# 3V3_BUCK.net
KiCad netlist of a schematic drawn in Altium Designer
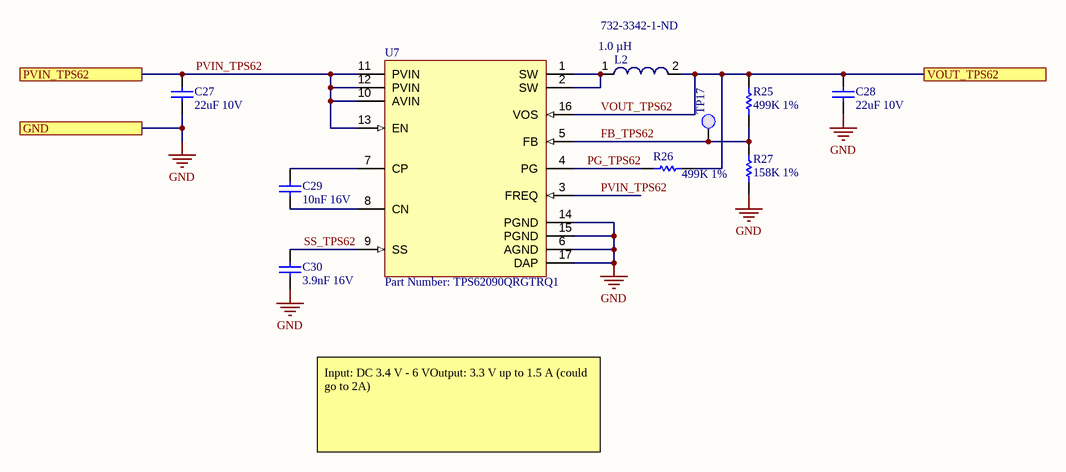
[diagram p0: 3V3_BUCK.SchDoc]

(export (version "E")
  (design (tool "Eeschema 10.0.6"))
  (components
    (comp (ref "C27")
      (value "22uF 10V")
      (footprint "CAPC0805(2012)145_N")
      (description "CAP 22uF 10V ±20% 0805 (2012 Metric) Thickness 1.45mm SMD")
      (fields (field (name "TOLERANCE") "Â±20%"))
      (libsource (lib "Altium Content Vault") (part "CAP"))
    )
    (comp (ref "C28")
      (value "22uF 10V")
      (footprint "CAPC0805(2012)145_N")
      (description "CAP 22uF 10V ±20% 0805 (2012 Metric) Thickness 1.45mm SMD")
      (fields (field (name "TOLERANCE") "Â±20%"))
      (libsource (lib "Altium Content Vault") (part "CAP"))
    )
    (comp (ref "C29")
      (value "10nF 16V")
      (footprint "CAPC0603(1608)100_N")
      (description "CAP 10nF 16V ±10% 0603 (1608 Metric) Thickness 1mm SMD")
      (fields (field (name "TOLERANCE") "Â±10%"))
      (libsource (lib "Altium Content Vault") (part "CAP"))
    )
    (comp (ref "C30")
      (value "3.9nF 16V")
      (footprint "CAPC0603(1608)100_N")
      (description "CAP 3.9nF 16V ±10% 0603 (1608 Metric) Thickness 1mm SMD")
      (fields (field (name "TOLERANCE") "Â±10%"))
      (libsource (lib "Altium Content Vault") (part "CAP"))
    )
    (comp (ref "L2")
      (value "74437324010")
      (footprint "WE-LHMI 4020")
      (description "SMD Power Inductor WE-LHMI, L=1.0 µH")
      (fields
        (field (name "INDUCTANCE") "1.0 µH")
        (field (name "MANUFACTURER") "Wuerth Elektronik")
        (field (name "SUPPLIER PART NUMBER 1") "732-3342-1-ND")
        (field (name "TOLERANCE") "20%")
      )
      (libsource (lib "Altium Content Vault") (part "WE-IND-INDUCTOR-2"))
    )
    (comp (ref "R25")
      (value "499K 1%")
      (footprint "RESC0603(1608)_L")
      (description "499K 0.1W 1% 0603 (1608 Metric)  SMD")
      (fields (field (name "TOLERANCE") "1 %") (field (name "POWER") "0.1 W"))
      (libsource (lib "Altium Content Vault") (part "RES"))
    )
    (comp (ref "R26")
      (value "499K 1%")
      (footprint "RESC0603(1608)_L")
      (description "499K 0.1W 1% 0603 (1608 Metric)  SMD")
      (fields (field (name "TOLERANCE") "1 %") (field (name "POWER") "0.1 W"))
      (libsource (lib "Altium Content Vault") (part "RES"))
    )
    (comp (ref "R27")
      (value "158K 1%")
      (footprint "RESC0603(1608)_N")
      (description "158K 0.1W 1% 0603 (1608 Metric)  SMD")
      (fields (field (name "TOLERANCE") "1 %") (field (name "POWER") "0.1 W"))
      (libsource (lib "Altium Content Vault") (part "RES"))
    )
    (comp (ref "TP17")
      (value "0.1\" Pad")
      (footprint "PCBComponent")
      (libsource (lib "Components - 12.02.20 - 18.05") (part "0.1{dblquote} Pad-A.4"))
    )
    (comp (ref "U7")
      (value "Part Number: TPS62090QRGTRQ1")
      (footprint "QFN50P300X300X100_HS-17N")
      (description "No Description Available")
      (fields
        (field (name "MANUFACTURER_PART_NUMBER") "TPS62090QRGTRQ1")
        (field (name "MANUFACTURER") "Texas Instruments")
        (field (name "COPYRIGHT") "Copyright (C) 2018 Accelerated Designs. All rights reserved")
      )
      (libsource (lib "2020-02-13_00-03-41") (part "TPS62090QRGTRQ1"))
    )
  )
  (nets
    (net (code "1") (name "/FB_TPS62") (class "Default")
      (node (ref "R25") (pin "1") (pinfunction "1_1") (pintype "passive"))
      (node (ref "R27") (pin "2") (pinfunction "2_2") (pintype "passive"))
      (node (ref "TP17") (pin "1") (pinfunction "PAD_1") (pintype "passive"))
      (node (ref "U7") (pin "5") (pinfunction "FB_5") (pintype "input"))
    )
    (net (code "2") (name "/PG_TPS62") (class "Default")
      (node (ref "R26") (pin "2") (pinfunction "2_2") (pintype "passive"))
      (node (ref "U7") (pin "4") (pinfunction "PG_4") (pintype "open_collector"))
    )
    (net (code "3") (name "/PVIN_TPS62") (class "Default")
      (node (ref "C27") (pin "2") (pinfunction "2_2") (pintype "passive"))
      (node (ref "U7") (pin "10") (pinfunction "AVIN_10") (pintype "power_in"))
      (node (ref "U7") (pin "11") (pinfunction "PVIN_11") (pintype "power_in"))
      (node (ref "U7") (pin "12") (pinfunction "PVIN_12") (pintype "power_in"))
      (node (ref "U7") (pin "13") (pinfunction "EN_13") (pintype "input"))
      (node (ref "U7") (pin "3") (pinfunction "FREQ_3") (pintype "input"))
    )
    (net (code "4") (name "/SS_TPS62") (class "Default")
      (node (ref "C30") (pin "2") (pinfunction "2_2") (pintype "passive"))
      (node (ref "U7") (pin "9") (pinfunction "SS_9") (pintype "input"))
    )
    (net (code "5") (name "/VOUT_TPS62") (class "Default")
      (node (ref "C28") (pin "2") (pinfunction "2_2") (pintype "passive"))
      (node (ref "L2") (pin "2") (pinfunction "2_2") (pintype "passive"))
      (node (ref "R25") (pin "2") (pinfunction "2_2") (pintype "passive"))
      (node (ref "R26") (pin "1") (pinfunction "1_1") (pintype "passive"))
      (node (ref "U7") (pin "16") (pinfunction "VOS_16") (pintype "input"))
    )
    (net (code "6") (name "GND") (class "Default")
      (node (ref "C27") (pin "1") (pinfunction "1_1") (pintype "passive"))
      (node (ref "C28") (pin "1") (pinfunction "1_1") (pintype "passive"))
      (node (ref "C30") (pin "1") (pinfunction "1_1") (pintype "passive"))
      (node (ref "R27") (pin "1") (pinfunction "1_1") (pintype "passive"))
      (node (ref "U7") (pin "14") (pinfunction "PGND_14") (pintype "power_in"))
      (node (ref "U7") (pin "15") (pinfunction "PGND_15") (pintype "power_in"))
      (node (ref "U7") (pin "17") (pinfunction "DAP_17") (pintype "power_in"))
      (node (ref "U7") (pin "6") (pinfunction "AGND_6") (pintype "power_in"))
    )
    (net (code "7") (name "Net-(L2-Pad1)") (class "Default")
      (node (ref "L2") (pin "1") (pinfunction "1_1") (pintype "passive"))
      (node (ref "U7") (pin "1") (pinfunction "SW_1") (pintype "power_in"))
      (node (ref "U7") (pin "2") (pinfunction "SW_2") (pintype "power_in"))
    )
    (net (code "8") (name "Net-(U7-CN)") (class "Default")
      (node (ref "C29") (pin "1") (pinfunction "1_1") (pintype "passive"))
      (node (ref "U7") (pin "8") (pinfunction "CN_8") (pintype "passive"))
    )
    (net (code "9") (name "Net-(U7-CP)") (class "Default")
      (node (ref "C29") (pin "2") (pinfunction "2_2") (pintype "passive"))
      (node (ref "U7") (pin "7") (pinfunction "CP_7") (pintype "passive"))
    )
  )
)
